# carl_ripup_2v42.net
KiCad netlist of a schematic drawn in EAGLE
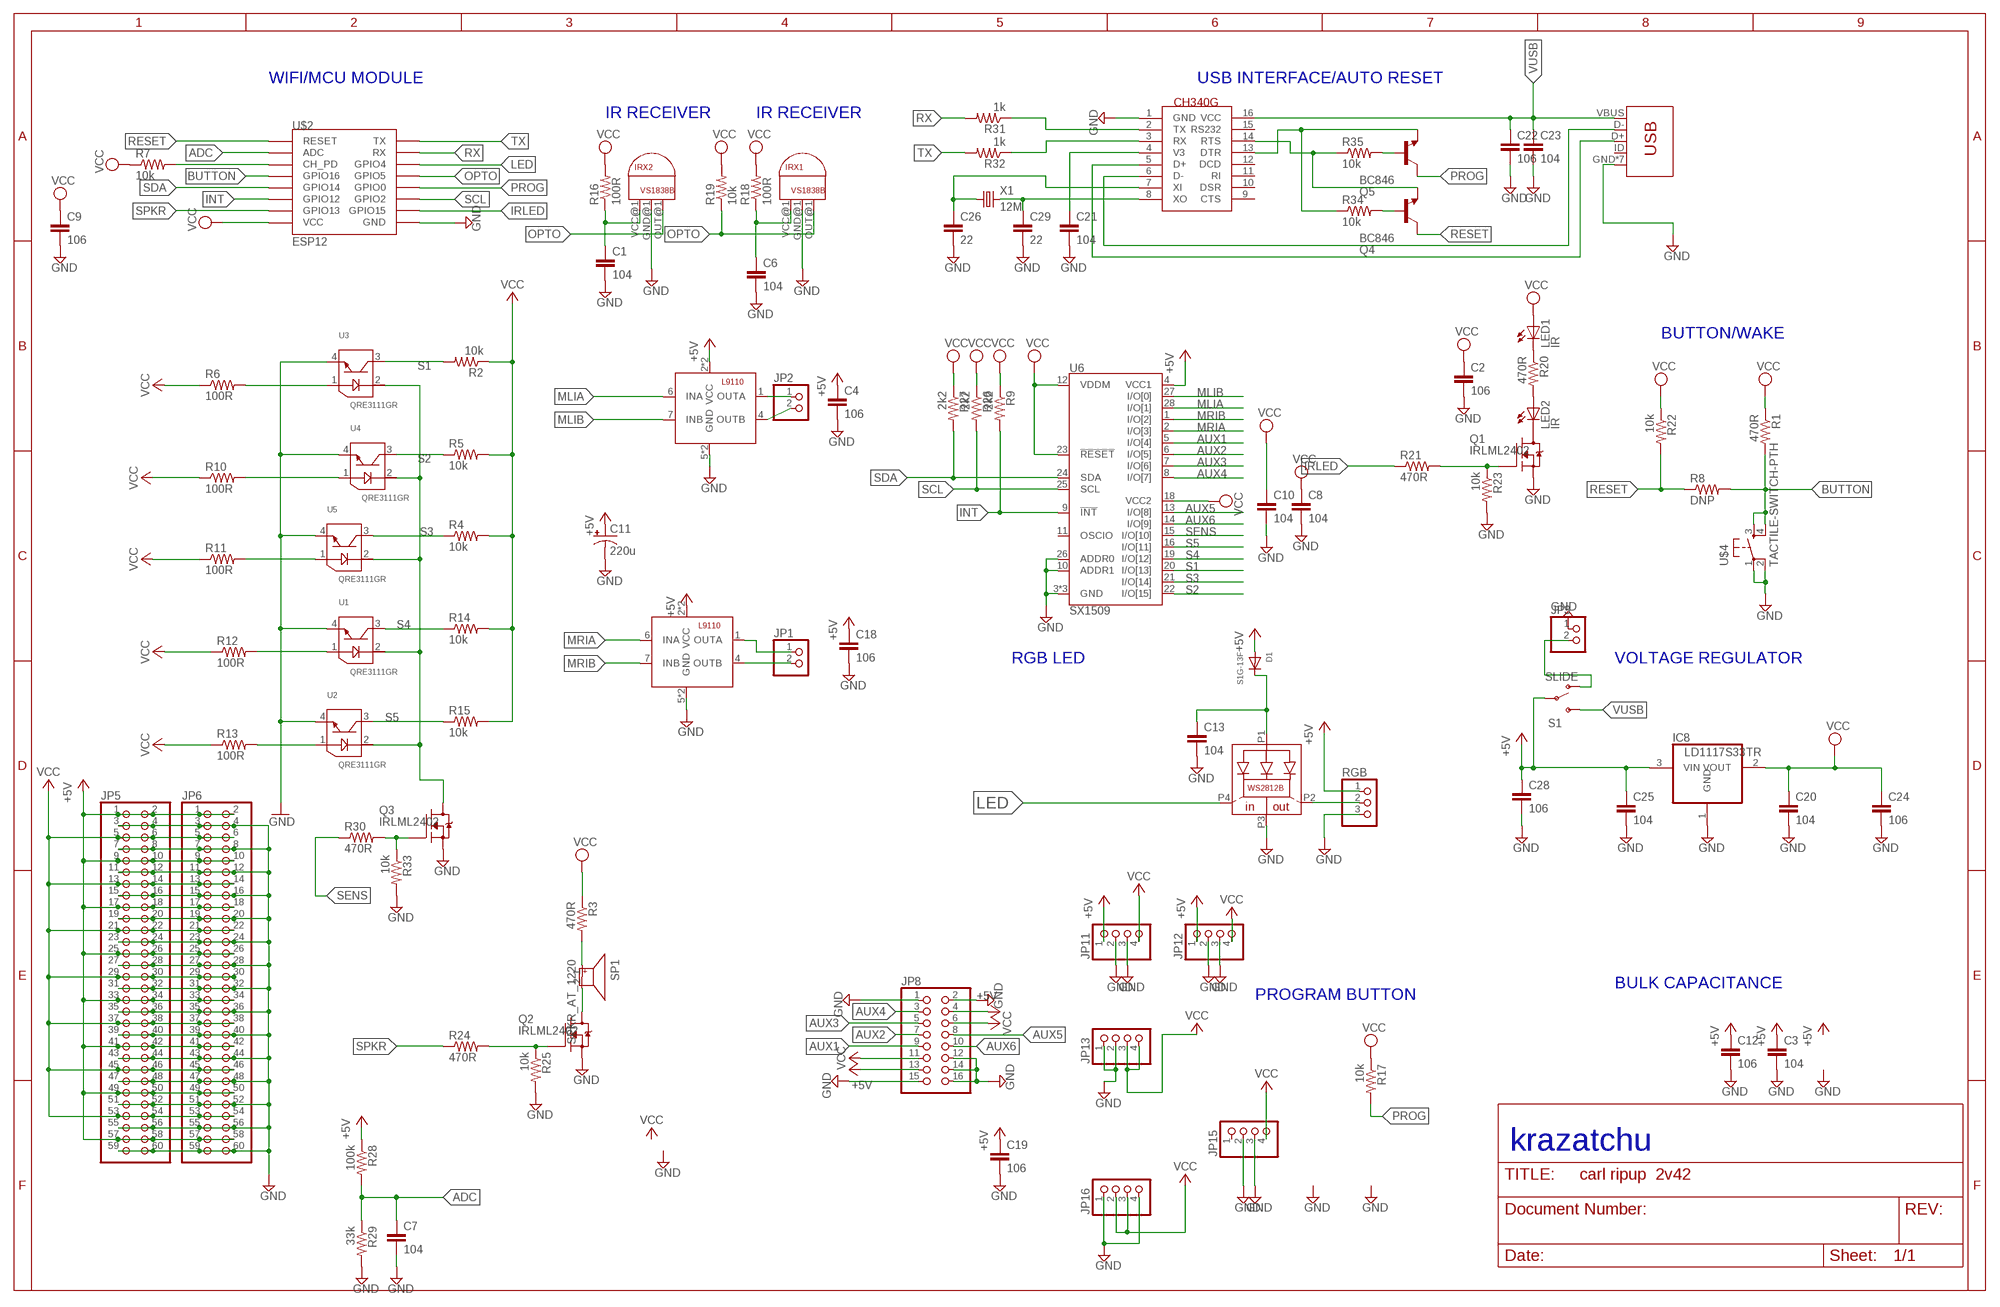
[diagram p0: schematic, sheet 1]

(export (version "E")
  (design (tool "Eeschema 10.0.6"))
  (components
    (comp (ref "C1")
      (value "104")
      (footprint "eagle-import:C0805")
      (libsource (lib "eagle-import") (part "C-EUC0805"))
    )
    (comp (ref "C2")
      (value "106")
      (footprint "eagle-import:C0805")
      (libsource (lib "eagle-import") (part "C-EUC0805"))
    )
    (comp (ref "C3")
      (value "104")
      (footprint "eagle-import:C0805")
      (libsource (lib "eagle-import") (part "C-EUC0805"))
    )
    (comp (ref "C4")
      (value "106")
      (footprint "eagle-import:C0805")
      (libsource (lib "eagle-import") (part "C-EUC0805"))
    )
    (comp (ref "C6")
      (value "104")
      (footprint "eagle-import:C0805")
      (libsource (lib "eagle-import") (part "C-EUC0805"))
    )
    (comp (ref "C7")
      (value "104")
      (footprint "eagle-import:C0805")
      (libsource (lib "eagle-import") (part "C-EUC0805"))
    )
    (comp (ref "C8")
      (value "104")
      (footprint "eagle-import:C0805")
      (libsource (lib "eagle-import") (part "C-EUC0805"))
    )
    (comp (ref "C9")
      (value "106")
      (footprint "eagle-import:C0805")
      (libsource (lib "eagle-import") (part "C-EUC0805"))
    )
    (comp (ref "C10")
      (value "104")
      (footprint "eagle-import:C0805")
      (libsource (lib "eagle-import") (part "C-EUC0805"))
    )
    (comp (ref "C11")
      (value "220u")
      (footprint "eagle-import:140CLH-0810")
      (libsource (lib "eagle-import") (part "CPOL-US140CLH-0810"))
    )
    (comp (ref "C12")
      (value "106")
      (footprint "eagle-import:C0805")
      (libsource (lib "eagle-import") (part "C-EUC0805"))
    )
    (comp (ref "C13")
      (value "104")
      (footprint "eagle-import:C0805")
      (libsource (lib "eagle-import") (part "C-EUC0805"))
    )
    (comp (ref "C18")
      (value "106")
      (footprint "eagle-import:C0805")
      (libsource (lib "eagle-import") (part "C-EUC0805"))
    )
    (comp (ref "C19")
      (value "106")
      (footprint "eagle-import:C0805")
      (libsource (lib "eagle-import") (part "C-EUC0805"))
    )
    (comp (ref "C20")
      (value "104")
      (footprint "eagle-import:C0805")
      (libsource (lib "eagle-import") (part "C-EUC0805"))
    )
    (comp (ref "C21")
      (value "104")
      (footprint "eagle-import:C0805")
      (libsource (lib "eagle-import") (part "C-EUC0805"))
    )
    (comp (ref "C22")
      (value "106")
      (footprint "eagle-import:C0805")
      (libsource (lib "eagle-import") (part "C-EUC0805"))
    )
    (comp (ref "C23")
      (value "104")
      (footprint "eagle-import:C0805")
      (libsource (lib "eagle-import") (part "C-EUC0805"))
    )
    (comp (ref "C24")
      (value "106")
      (footprint "eagle-import:C0805")
      (libsource (lib "eagle-import") (part "C-EUC0805"))
    )
    (comp (ref "C25")
      (value "104")
      (footprint "eagle-import:C0805")
      (libsource (lib "eagle-import") (part "C-EUC0805"))
    )
    (comp (ref "C26")
      (value "22")
      (footprint "eagle-import:C0805")
      (libsource (lib "eagle-import") (part "C-EUC0805"))
    )
    (comp (ref "C28")
      (value "106")
      (footprint "eagle-import:C0805")
      (libsource (lib "eagle-import") (part "C-EUC0805"))
    )
    (comp (ref "C29")
      (value "22")
      (footprint "eagle-import:C0805")
      (libsource (lib "eagle-import") (part "C-EUC0805"))
    )
    (comp (ref "D1")
      (value "S1G-13F")
      (footprint "eagle-import:SMADIODE")
      (libsource (lib "eagle-import") (part "DIODESMA"))
    )
    (comp (ref "IC1")
      (value "L9110")
      (footprint "eagle-import:SOIC8")
      (libsource (lib "eagle-import") (part "L9110"))
    )
    (comp (ref "IC2")
      (value "L9110")
      (footprint "eagle-import:SOIC8")
      (libsource (lib "eagle-import") (part "L9110"))
    )
    (comp (ref "IC8")
      (value "LD1117S33TR")
      (footprint "eagle-import:SOT223")
      (fields (field (name "MPN") "REG1117"))
      (libsource (lib "eagle-import") (part "REG1117"))
    )
    (comp (ref "IRX1")
      (value "VS1838B")
      (footprint "eagle-import:IR-RX-SINGLE")
      (libsource (lib "eagle-import") (part "IR-RX"))
    )
    (comp (ref "IRX2")
      (value "VS1838B")
      (footprint "eagle-import:IR-RX-SINGLE")
      (libsource (lib "eagle-import") (part "IR-RX"))
    )
    (comp (ref "JP1")
      (value "PINHD-1X2")
      (footprint "eagle-import:1X02")
      (libsource (lib "eagle-import") (part "PINHD-1X2"))
    )
    (comp (ref "JP2")
      (value "PINHD-1X2")
      (footprint "eagle-import:1X02")
      (libsource (lib "eagle-import") (part "PINHD-1X2"))
    )
    (comp (ref "JP3")
      (value "PINHD-1X2")
      (footprint "eagle-import:1X02")
      (libsource (lib "eagle-import") (part "PINHD-1X2"))
    )
    (comp (ref "JP5")
      (value "PINHD-2X30")
      (footprint "eagle-import:2X30")
      (libsource (lib "eagle-import") (part "PINHD-2X30"))
    )
    (comp (ref "JP6")
      (value "PINHD-2X30")
      (footprint "eagle-import:2X30")
      (libsource (lib "eagle-import") (part "PINHD-2X30"))
    )
    (comp (ref "JP8")
      (value "PINHD-2X8")
      (footprint "eagle-import:2X08")
      (libsource (lib "eagle-import") (part "PINHD-2X8"))
    )
    (comp (ref "JP11")
      (value "PINHD-1X4")
      (footprint "eagle-import:1X04")
      (libsource (lib "eagle-import") (part "PINHD-1X4"))
    )
    (comp (ref "JP12")
      (value "PINHD-1X4")
      (footprint "eagle-import:1X04")
      (libsource (lib "eagle-import") (part "PINHD-1X4"))
    )
    (comp (ref "JP13")
      (value "PINHD-1X4")
      (footprint "eagle-import:1X04")
      (libsource (lib "eagle-import") (part "PINHD-1X4"))
    )
    (comp (ref "JP15")
      (value "PINHD-1X4")
      (footprint "eagle-import:1X04")
      (libsource (lib "eagle-import") (part "PINHD-1X4"))
    )
    (comp (ref "JP16")
      (value "PINHD-1X4")
      (footprint "eagle-import:1X04")
      (libsource (lib "eagle-import") (part "PINHD-1X4"))
    )
    (comp (ref "LED1")
      (value "IR")
      (footprint "eagle-import:LED5MM")
      (libsource (lib "eagle-import") (part "LED5MM"))
    )
    (comp (ref "LED2")
      (value "IR")
      (footprint "eagle-import:LED5MM")
      (libsource (lib "eagle-import") (part "LED5MM"))
    )
    (comp (ref "Q1")
      (value "IRLML2402")
      (footprint "eagle-import:SOT23")
      (libsource (lib "eagle-import") (part "IRLML2402"))
    )
    (comp (ref "Q2")
      (value "IRLML2402")
      (footprint "eagle-import:SOT23")
      (libsource (lib "eagle-import") (part "IRLML2402"))
    )
    (comp (ref "Q3")
      (value "IRLML2402")
      (footprint "eagle-import:SOT23")
      (libsource (lib "eagle-import") (part "IRLML2402"))
    )
    (comp (ref "Q4")
      (value "BC846")
      (footprint "eagle-import:SOT23")
      (libsource (lib "eagle-import") (part "BC846"))
    )
    (comp (ref "Q5")
      (value "BC846")
      (footprint "eagle-import:SOT23")
      (libsource (lib "eagle-import") (part "BC846"))
    )
    (comp (ref "R1")
      (value "470R")
      (footprint "eagle-import:R0805")
      (libsource (lib "eagle-import") (part "rcl_R-US_R0805"))
    )
    (comp (ref "R2")
      (value "10k")
      (footprint "eagle-import:R0805")
      (libsource (lib "eagle-import") (part "R-US_R0805"))
    )
    (comp (ref "R3")
      (value "470R")
      (footprint "eagle-import:R0805")
      (libsource (lib "eagle-import") (part "rcl_R-US_R0805"))
    )
    (comp (ref "R4")
      (value "10k")
      (footprint "eagle-import:R0805")
      (libsource (lib "eagle-import") (part "R-US_R0805"))
    )
    (comp (ref "R5")
      (value "10k")
      (footprint "eagle-import:R0805")
      (libsource (lib "eagle-import") (part "R-US_R0805"))
    )
    (comp (ref "R6")
      (value "100R")
      (footprint "eagle-import:R0805")
      (libsource (lib "eagle-import") (part "R-US_R0805"))
    )
    (comp (ref "R7")
      (value "10k")
      (footprint "eagle-import:R0805")
      (libsource (lib "eagle-import") (part "rcl_R-US_R0805"))
    )
    (comp (ref "R8")
      (value "DNP")
      (footprint "eagle-import:R0805")
      (libsource (lib "eagle-import") (part "rcl_R-US_R0805"))
    )
    (comp (ref "R9")
      (value "2k2")
      (footprint "eagle-import:R0805")
      (libsource (lib "eagle-import") (part "rcl_R-US_R0805"))
    )
    (comp (ref "R10")
      (value "100R")
      (footprint "eagle-import:R0805")
      (libsource (lib "eagle-import") (part "R-US_R0805"))
    )
    (comp (ref "R11")
      (value "100R")
      (footprint "eagle-import:R0805")
      (libsource (lib "eagle-import") (part "R-US_R0805"))
    )
    (comp (ref "R12")
      (value "100R")
      (footprint "eagle-import:R0805")
      (libsource (lib "eagle-import") (part "R-US_R0805"))
    )
    (comp (ref "R13")
      (value "100R")
      (footprint "eagle-import:R0805")
      (libsource (lib "eagle-import") (part "R-US_R0805"))
    )
    (comp (ref "R14")
      (value "10k")
      (footprint "eagle-import:R0805")
      (libsource (lib "eagle-import") (part "R-US_R0805"))
    )
    (comp (ref "R15")
      (value "10k")
      (footprint "eagle-import:R0805")
      (libsource (lib "eagle-import") (part "R-US_R0805"))
    )
    (comp (ref "R16")
      (value "100R")
      (footprint "eagle-import:R0805")
      (libsource (lib "eagle-import") (part "rcl_R-US_R0805"))
    )
    (comp (ref "R17")
      (value "10k")
      (footprint "eagle-import:R0805")
      (libsource (lib "eagle-import") (part "rcl_R-US_R0805"))
    )
    (comp (ref "R18")
      (value "100R")
      (footprint "eagle-import:R0805")
      (libsource (lib "eagle-import") (part "rcl_R-US_R0805"))
    )
    (comp (ref "R19")
      (value "10k")
      (footprint "eagle-import:R0805")
      (libsource (lib "eagle-import") (part "rcl_R-US_R0805"))
    )
    (comp (ref "R20")
      (value "470R")
      (footprint "eagle-import:R0805")
      (libsource (lib "eagle-import") (part "rcl_R-US_R0805"))
    )
    (comp (ref "R21")
      (value "470R")
      (footprint "eagle-import:R0805")
      (libsource (lib "eagle-import") (part "rcl_R-US_R0805"))
    )
    (comp (ref "R22")
      (value "10k")
      (footprint "eagle-import:R0805")
      (libsource (lib "eagle-import") (part "rcl_R-US_R0805"))
    )
    (comp (ref "R23")
      (value "10k")
      (footprint "eagle-import:R0805")
      (libsource (lib "eagle-import") (part "rcl_R-US_R0805"))
    )
    (comp (ref "R24")
      (value "470R")
      (footprint "eagle-import:R0805")
      (libsource (lib "eagle-import") (part "rcl_R-US_R0805"))
    )
    (comp (ref "R25")
      (value "10k")
      (footprint "eagle-import:R0805")
      (libsource (lib "eagle-import") (part "rcl_R-US_R0805"))
    )
    (comp (ref "R26")
      (value "2k2")
      (footprint "eagle-import:R0805")
      (libsource (lib "eagle-import") (part "rcl_R-US_R0805"))
    )
    (comp (ref "R27")
      (value "2k2")
      (footprint "eagle-import:R0805")
      (libsource (lib "eagle-import") (part "rcl_R-US_R0805"))
    )
    (comp (ref "R28")
      (value "100k")
      (footprint "eagle-import:R0805")
      (libsource (lib "eagle-import") (part "rcl_R-US_R0805"))
    )
    (comp (ref "R29")
      (value "33k")
      (footprint "eagle-import:R0805")
      (libsource (lib "eagle-import") (part "rcl_R-US_R0805"))
    )
    (comp (ref "R30")
      (value "470R")
      (footprint "eagle-import:R0805")
      (libsource (lib "eagle-import") (part "rcl_R-US_R0805"))
    )
    (comp (ref "R31")
      (value "1k")
      (footprint "eagle-import:R0805")
      (libsource (lib "eagle-import") (part "rcl_R-US_R0805"))
    )
    (comp (ref "R32")
      (value "1k")
      (footprint "eagle-import:R0805")
      (libsource (lib "eagle-import") (part "rcl_R-US_R0805"))
    )
    (comp (ref "R33")
      (value "10k")
      (footprint "eagle-import:R0805")
      (libsource (lib "eagle-import") (part "rcl_R-US_R0805"))
    )
    (comp (ref "R34")
      (value "10k")
      (footprint "eagle-import:R0805")
      (libsource (lib "eagle-import") (part "rcl_R-US_R0805"))
    )
    (comp (ref "R35")
      (value "10k")
      (footprint "eagle-import:R0805")
      (libsource (lib "eagle-import") (part "rcl_R-US_R0805"))
    )
    (comp (ref "RGB")
      (value "PINHD-1X3RND")
      (footprint "eagle-import:1X03_ROUND")
      (libsource (lib "eagle-import") (part "PINHD-1X3RND"))
    )
    (comp (ref "RGB1")
      (value "ws2812b")
      (footprint "eagle-import:PLCC_4_5050_TRIM")
      (libsource (lib "eagle-import") (part "WS2812B"))
    )
    (comp (ref "S1")
      (value "SLIDE")
      (footprint "eagle-import:SWITCH-SPDT")
      (libsource (lib "eagle-import") (part "SWITCH-SPDTPTH"))
    )
    (comp (ref "SP1")
      (value "SPKR_AT_1220")
      (footprint "eagle-import:TRANSDUCER_12_6")
      (libsource (lib "eagle-import") (part "SPKR_AT_1220"))
    )
    (comp (ref "U$2")
      (value "ESP12")
      (footprint "eagle-import:ESP12")
      (libsource (lib "eagle-import") (part "ESP12"))
    )
    (comp (ref "U$4")
      (value "TACTILE-SWITCH-PTH")
      (footprint "eagle-import:TAC-SWITCH-PTH")
      (libsource (lib "eagle-import") (part "TACTILE-SWITCH-PTH"))
    )
    (comp (ref "U$5")
      (value "CH340G")
      (footprint "eagle-import:SOIC16")
      (libsource (lib "eagle-import") (part "CH340G"))
    )
    (comp (ref "U1")
      (value "QRE3111GR")
      (footprint "eagle-import:QRE1113GR")
      (libsource (lib "eagle-import") (part "QRE3111GR"))
    )
    (comp (ref "U2")
      (value "QRE3111GR")
      (footprint "eagle-import:QRE1113GR")
      (libsource (lib "eagle-import") (part "QRE3111GR"))
    )
    (comp (ref "U3")
      (value "QRE3111GR")
      (footprint "eagle-import:QRE1113GR")
      (libsource (lib "eagle-import") (part "QRE3111GR"))
    )
    (comp (ref "U4")
      (value "QRE3111GR")
      (footprint "eagle-import:QRE1113GR")
      (libsource (lib "eagle-import") (part "QRE3111GR"))
    )
    (comp (ref "U5")
      (value "QRE3111GR")
      (footprint "eagle-import:QRE1113GR")
      (libsource (lib "eagle-import") (part "QRE3111GR"))
    )
    (comp (ref "U6")
      (value "SX1509")
      (footprint "eagle-import:QFN-28")
      (libsource (lib "eagle-import") (part "SX1509"))
    )
    (comp (ref "USB1")
      (value "USB_MICROB-10118194-0001LF")
      (footprint "eagle-import:USB-MICRO-B")
      (libsource (lib "eagle-import") (part "USB_MICROB-10118194-0001LF"))
    )
    (comp (ref "X1")
      (value "12M")
      (footprint "eagle-import:HC49UP")
      (libsource (lib "eagle-import") (part "CRYSTALHC49UP"))
    )
  )
  (nets
    (net (code "1") (name "+5V") (class "Default")
      (node (ref "C11") (pin "+") (pinfunction "+_+") (pintype "passive"))
      (node (ref "C12") (pin "1") (pinfunction "1_1") (pintype "passive"))
      (node (ref "C18") (pin "1") (pinfunction "1_1") (pintype "passive"))
      (node (ref "C19") (pin "1") (pinfunction "1_1") (pintype "passive"))
      (node (ref "C25") (pin "1") (pinfunction "1_1") (pintype "passive"))
      (node (ref "C28") (pin "1") (pinfunction "1_1") (pintype "passive"))
      (node (ref "C3") (pin "1") (pinfunction "1_1") (pintype "passive"))
      (node (ref "C4") (pin "1") (pinfunction "1_1") (pintype "passive"))
      (node (ref "D1") (pin "A") (pinfunction "A_A") (pintype "passive"))
      (node (ref "IC1") (pin "2") (pinfunction "VCC_2") (pintype "bidirectional"))
      (node (ref "IC1") (pin "3") (pinfunction "VCC_3") (pintype "bidirectional"))
      (node (ref "IC2") (pin "2") (pinfunction "VCC_2") (pintype "bidirectional"))
      (node (ref "IC2") (pin "3") (pinfunction "VCC_3") (pintype "bidirectional"))
      (node (ref "IC8") (pin "3") (pinfunction "VIN_3") (pintype "input"))
      (node (ref "JP11") (pin "1") (pinfunction "1_1") (pintype "passive"))
      (node (ref "JP12") (pin "1") (pinfunction "1_1") (pintype "passive"))
      (node (ref "JP5") (pin "1") (pinfunction "1_1") (pintype "passive"))
      (node (ref "JP5") (pin "10") (pinfunction "10_10") (pintype "passive"))
      (node (ref "JP5") (pin "17") (pinfunction "17_17") (pintype "passive"))
      (node (ref "JP5") (pin "18") (pinfunction "18_18") (pintype "passive"))
      (node (ref "JP5") (pin "2") (pinfunction "2_2") (pintype "passive"))
      (node (ref "JP5") (pin "25") (pinfunction "25_25") (pintype "passive"))
      (node (ref "JP5") (pin "26") (pinfunction "26_26") (pintype "passive"))
      (node (ref "JP5") (pin "33") (pinfunction "33_33") (pintype "passive"))
      (node (ref "JP5") (pin "34") (pinfunction "34_34") (pintype "passive"))
      (node (ref "JP5") (pin "41") (pinfunction "41_41") (pintype "passive"))
      (node (ref "JP5") (pin "42") (pinfunction "42_42") (pintype "passive"))
      (node (ref "JP5") (pin "49") (pinfunction "49_49") (pintype "passive"))
      (node (ref "JP5") (pin "50") (pinfunction "50_50") (pintype "passive"))
      (node (ref "JP5") (pin "57") (pinfunction "57_57") (pintype "passive"))
      (node (ref "JP5") (pin "58") (pinfunction "58_58") (pintype "passive"))
      (node (ref "JP5") (pin "9") (pinfunction "9_9") (pintype "passive"))
      (node (ref "JP6") (pin "1") (pinfunction "1_1") (pintype "passive"))
      (node (ref "JP6") (pin "10") (pinfunction "10_10") (pintype "passive"))
      (node (ref "JP6") (pin "17") (pinfunction "17_17") (pintype "passive"))
      (node (ref "JP6") (pin "18") (pinfunction "18_18") (pintype "passive"))
      (node (ref "JP6") (pin "2") (pinfunction "2_2") (pintype "passive"))
      (node (ref "JP6") (pin "25") (pinfunction "25_25") (pintype "passive"))
      (node (ref "JP6") (pin "26") (pinfunction "26_26") (pintype "passive"))
      (node (ref "JP6") (pin "33") (pinfunction "33_33") (pintype "passive"))
      (node (ref "JP6") (pin "34") (pinfunction "34_34") (pintype "passive"))
      (node (ref "JP6") (pin "41") (pinfunction "41_41") (pintype "passive"))
      (node (ref "JP6") (pin "42") (pinfunction "42_42") (pintype "passive"))
      (node (ref "JP6") (pin "49") (pinfunction "49_49") (pintype "passive"))
      (node (ref "JP6") (pin "50") (pinfunction "50_50") (pintype "passive"))
      (node (ref "JP6") (pin "57") (pinfunction "57_57") (pintype "passive"))
      (node (ref "JP6") (pin "58") (pinfunction "58_58") (pintype "passive"))
      (node (ref "JP6") (pin "9") (pinfunction "9_9") (pintype "passive"))
      (node (ref "JP8") (pin "13") (pinfunction "13_13") (pintype "passive"))
      (node (ref "JP8") (pin "4") (pinfunction "4_4") (pintype "passive"))
      (node (ref "R28") (pin "1") (pinfunction "1_1") (pintype "passive"))
      (node (ref "RGB") (pin "1") (pinfunction "1_1") (pintype "passive"))
      (node (ref "S1") (pin "2") (pinfunction "P_2") (pintype "passive"))
      (node (ref "U6") (pin "4") (pinfunction "VCC1_4") (pintype "bidirectional"))
    )
    (net (code "2") (name "/S1") (class "Default")
      (node (ref "R2") (pin "2") (pinfunction "2_2") (pintype "passive"))
      (node (ref "U3") (pin "3") (pinfunction "3_3") (pintype "bidirectional"))
      (node (ref "U6") (pin "20") (pinfunction "I/O[13]_20") (pintype "bidirectional"))
    )
    (net (code "3") (name "/S2") (class "Default")
      (node (ref "R5") (pin "1") (pinfunction "1_1") (pintype "passive"))
      (node (ref "U4") (pin "3") (pinfunction "3_3") (pintype "bidirectional"))
      (node (ref "U6") (pin "22") (pinfunction "I/O[15]_22") (pintype "bidirectional"))
    )
    (net (code "4") (name "/S3") (class "Default")
      (node (ref "R4") (pin "1") (pinfunction "1_1") (pintype "passive"))
      (node (ref "U5") (pin "3") (pinfunction "3_3") (pintype "bidirectional"))
      (node (ref "U6") (pin "21") (pinfunction "I/O[14]_21") (pintype "bidirectional"))
    )
    (net (code "5") (name "/S4") (class "Default")
      (node (ref "R14") (pin "1") (pinfunction "1_1") (pintype "passive"))
      (node (ref "U1") (pin "3") (pinfunction "3_3") (pintype "bidirectional"))
      (node (ref "U6") (pin "19") (pinfunction "I/O[12]_19") (pintype "bidirectional"))
    )
    (net (code "6") (name "/S5") (class "Default")
      (node (ref "R15") (pin "1") (pinfunction "1_1") (pintype "passive"))
      (node (ref "U2") (pin "3") (pinfunction "3_3") (pintype "bidirectional"))
      (node (ref "U6") (pin "16") (pinfunction "I/O[11]_16") (pintype "bidirectional"))
    )
    (net (code "7") (name "ADC") (class "Default")
      (node (ref "C7") (pin "1") (pinfunction "1_1") (pintype "passive"))
      (node (ref "R28") (pin "2") (pinfunction "2_2") (pintype "passive"))
      (node (ref "R29") (pin "1") (pinfunction "1_1") (pintype "passive"))
      (node (ref "U$2") (pin "ADC") (pinfunction "ADC_ADC") (pintype "bidirectional"))
    )
    (net (code "8") (name "AUX1") (class "Default")
      (node (ref "JP8") (pin "9") (pinfunction "9_9") (pintype "passive"))
      (node (ref "U6") (pin "5") (pinfunction "I/O[4]_5") (pintype "bidirectional"))
    )
    (net (code "9") (name "AUX2") (class "Default")
      (node (ref "JP8") (pin "7") (pinfunction "7_7") (pintype "passive"))
      (node (ref "U6") (pin "6") (pinfunction "I/O[5]_6") (pintype "bidirectional"))
    )
    (net (code "10") (name "AUX3") (class "Default")
      (node (ref "JP8") (pin "5") (pinfunction "5_5") (pintype "passive"))
      (node (ref "U6") (pin "7") (pinfunction "I/O[6]_7") (pintype "bidirectional"))
    )
    (net (code "11") (name "AUX4") (class "Default")
      (node (ref "JP8") (pin "3") (pinfunction "3_3") (pintype "passive"))
      (node (ref "U6") (pin "8") (pinfunction "I/O[7]_8") (pintype "bidirectional"))
    )
    (net (code "12") (name "AUX5") (class "Default")
      (node (ref "JP8") (pin "8") (pinfunction "8_8") (pintype "passive"))
      (node (ref "U6") (pin "13") (pinfunction "I/O[8]_13") (pintype "bidirectional"))
    )
    (net (code "13") (name "AUX6") (class "Default")
      (node (ref "JP8") (pin "10") (pinfunction "10_10") (pintype "passive"))
      (node (ref "U6") (pin "14") (pinfunction "I/O[9]_14") (pintype "bidirectional"))
    )
    (net (code "14") (name "BUTTON") (class "Default")
      (node (ref "R1") (pin "2") (pinfunction "2_2") (pintype "passive"))
      (node (ref "R8") (pin "2") (pinfunction "2_2") (pintype "passive"))
      (node (ref "U$2") (pin "GPIO16") (pinfunction "GPIO16_GPIO16") (pintype "bidirectional"))
      (node (ref "U$4") (pin "3") (pinfunction "3_3") (pintype "passive"))
      (node (ref "U$4") (pin "4") (pinfunction "4_4") (pintype "passive"))
    )
    (net (code "15") (name "GND") (class "Default")
      (node (ref "C1") (pin "2") (pinfunction "2_2") (pintype "passive"))
      (node (ref "C10") (pin "2") (pinfunction "2_2") (pintype "passive"))
      (node (ref "C11") (pin "-") (pinfunction "-_-") (pintype "passive"))
      (node (ref "C12") (pin "2") (pinfunction "2_2") (pintype "passive"))
      (node (ref "C13") (pin "2") (pinfunction "2_2") (pintype "passive"))
      (node (ref "C18") (pin "2") (pinfunction "2_2") (pintype "passive"))
      (node (ref "C19") (pin "2") (pinfunction "2_2") (pintype "passive"))
      (node (ref "C2") (pin "2") (pinfunction "2_2") (pintype "passive"))
      (node (ref "C20") (pin "2") (pinfunction "2_2") (pintype "passive"))
      (node (ref "C21") (pin "2") (pinfunction "2_2") (pintype "passive"))
      (node (ref "C22") (pin "2") (pinfunction "2_2") (pintype "passive"))
      (node (ref "C23") (pin "2") (pinfunction "2_2") (pintype "passive"))
      (node (ref "C24") (pin "2") (pinfunction "2_2") (pintype "passive"))
      (node (ref "C25") (pin "2") (pinfunction "2_2") (pintype "passive"))
      (node (ref "C26") (pin "2") (pinfunction "2_2") (pintype "passive"))
      (node (ref "C28") (pin "2") (pinfunction "2_2") (pintype "passive"))
      (node (ref "C29") (pin "2") (pinfunction "2_2") (pintype "passive"))
      (node (ref "C3") (pin "2") (pinfunction "2_2") (pintype "passive"))
      (node (ref "C4") (pin "2") (pinfunction "2_2") (pintype "passive"))
      (node (ref "C6") (pin "2") (pinfunction "2_2") (pintype "passive"))
      (node (ref "C7") (pin "2") (pinfunction "2_2") (pintype "passive"))
      (node (ref "C8") (pin "2") (pinfunction "2_2") (pintype "passive"))
      (node (ref "C9") (pin "2") (pinfunction "2_2") (pintype "passive"))
      (node (ref "IC1") (pin "5") (pinfunction "GND_5") (pintype "bidirectional"))
      (node (ref "IC1") (pin "8") (pinfunction "GND_8") (pintype "bidirectional"))
      (node (ref "IC2") (pin "5") (pinfunction "GND_5") (pintype "bidirectional"))
      (node (ref "IC2") (pin "8") (pinfunction "GND_8") (pintype "bidirectional"))
      (node (ref "IC8") (pin "1") (pinfunction "GND_1") (pintype "power_in"))
      (node (ref "IRX1") (pin "GND@1") (pinfunction "GND_GND@1") (pintype "bidirectional"))
      (node (ref "IRX2") (pin "GND@1") (pinfunction "GND_GND@1") (pintype "bidirectional"))
      (node (ref "JP11") (pin "2") (pinfunction "2_2") (pintype "passive"))
      (node (ref "JP11") (pin "3") (pinfunction "3_3") (pintype "passive"))
      (node (ref "JP12") (pin "2") (pinfunction "2_2") (pintype "passive"))
      (node (ref "JP12") (pin "3") (pinfunction "3_3") (pintype "passive"))
      (node (ref "JP13") (pin "1") (pinfunction "1_1") (pintype "passive"))
      (node (ref "JP13") (pin "2") (pinfunction "2_2") (pintype "passive"))
      (node (ref "JP15") (pin "2") (pinfunction "2_2") (pintype "passive"))
      (node (ref "JP15") (pin "3") (pinfunction "3_3") (pintype "passive"))
      (node (ref "JP16") (pin "1") (pinfunction "1_1") (pintype "passive"))
      (node (ref "JP16") (pin "4") (pinfunction "4_4") (pintype "passive"))
      (node (ref "JP3") (pin "1") (pinfunction "1_1") (pintype "passive"))
      (node (ref "JP5") (pin "11") (pinfunction "11_11") (pintype "passive"))
      (node (ref "JP5") (pin "12") (pinfunction "12_12") (pintype "passive"))
      (node (ref "JP5") (pin "15") (pinfunction "15_15") (pintype "passive"))
      (node (ref "JP5") (pin "16") (pinfunction "16_16") (pintype "passive"))
      (node (ref "JP5") (pin "19") (pinfunction "19_19") (pintype "passive"))
      (node (ref "JP5") (pin "20") (pinfunction "20_20") (pintype "passive"))
      (node (ref "JP5") (pin "23") (pinfunction "23_23") (pintype "passive"))
      (node (ref "JP5") (pin "24") (pinfunction "24_24") (pintype "passive"))
      (node (ref "JP5") (pin "27") (pinfunction "27_27") (pintype "passive"))
      (node (ref "JP5") (pin "28") (pinfunction "28_28") (pintype "passive"))
      (node (ref "JP5") (pin "3") (pinfunction "3_3") (pintype "passive"))
      (node (ref "JP5") (pin "31") (pinfunction "31_31") (pintype "passive"))
      (node (ref "JP5") (pin "32") (pinfunction "32_32") (pintype "passive"))
      (node (ref "JP5") (pin "35") (pinfunction "35_35") (pintype "passive"))
      (node (ref "JP5") (pin "36") (pinfunction "36_36") (pintype "passive"))
      (node (ref "JP5") (pin "39") (pinfunction "39_39") (pintype "passive"))
      (node (ref "JP5") (pin "4") (pinfunction "4_4") (pintype "passive"))
      (node (ref "JP5") (pin "40") (pinfunction "40_40") (pintype "passive"))
      (node (ref "JP5") (pin "43") (pinfunction "43_43") (pintype "passive"))
      (node (ref "JP5") (pin "44") (pinfunction "44_44") (pintype "passive"))
      (node (ref "JP5") (pin "47") (pinfunction "47_47") (pintype "passive"))
      (node (ref "JP5") (pin "48") (pinfunction "48_48") (pintype "passive"))
      (node (ref "JP5") (pin "51") (pinfunction "51_51") (pintype "passive"))
      (node (ref "JP5") (pin "52") (pinfunction "52_52") (pintype "passive"))
      (node (ref "JP5") (pin "55") (pinfunction "55_55") (pintype "passive"))
      (node (ref "JP5") (pin "56") (pinfunction "56_56") (pintype "passive"))
      (node (ref "JP5") (pin "59") (pinfunction "59_59") (pintype "passive"))
      (node (ref "JP5") (pin "60") (pinfunction "60_60") (pintype "passive"))
      (node (ref "JP5") (pin "7") (pinfunction "7_7") (pintype "passive"))
      (node (ref "JP5") (pin "8") (pinfunction "8_8") (pintype "passive"))
      (node (ref "JP6") (pin "11") (pinfunction "11_11") (pintype "passive"))
      (node (ref "JP6") (pin "12") (pinfunction "12_12") (pintype "passive"))
      (node (ref "JP6") (pin "15") (pinfunction "15_15") (pintype "passive"))
      (node (ref "JP6") (pin "16") (pinfunction "16_16") (pintype "passive"))
      (node (ref "JP6") (pin "19") (pinfunction "19_19") (pintype "passive"))
      (node (ref "JP6") (pin "20") (pinfunction "20_20") (pintype "passive"))
      (node (ref "JP6") (pin "23") (pinfunction "23_23") (pintype "passive"))
      (node (ref "JP6") (pin "24") (pinfunction "24_24") (pintype "passive"))
      (node (ref "JP6") (pin "27") (pinfunction "27_27") (pintype "passive"))
      (node (ref "JP6") (pin "28") (pinfunction "28_28") (pintype "passive"))
      (node (ref "JP6") (pin "3") (pinfunction "3_3") (pintype "passive"))
      (node (ref "JP6") (pin "31") (pinfunction "31_31") (pintype "passive"))
      (node (ref "JP6") (pin "32") (pinfunction "32_32") (pintype "passive"))
      (node (ref "JP6") (pin "35") (pinfunction "35_35") (pintype "passive"))
      (node (ref "JP6") (pin "36") (pinfunction "36_36") (pintype "passive"))
      (node (ref "JP6") (pin "39") (pinfunction "39_39") (pintype "passive"))
      (node (ref "JP6") (pin "4") (pinfunction "4_4") (pintype "passive"))
      (node (ref "JP6") (pin "40") (pinfunction "40_40") (pintype "passive"))
      (node (ref "JP6") (pin "43") (pinfunction "43_43") (pintype "passive"))
      (node (ref "JP6") (pin "44") (pinfunction "44_44") (pintype "passive"))
      (node (ref "JP6") (pin "47") (pinfunction "47_47") (pintype "passive"))
      (node (ref "JP6") (pin "48") (pinfunction "48_48") (pintype "passive"))
      (node (ref "JP6") (pin "51") (pinfunction "51_51") (pintype "passive"))
      (node (ref "JP6") (pin "52") (pinfunction "52_52") (pintype "passive"))
      (node (ref "JP6") (pin "55") (pinfunction "55_55") (pintype "passive"))
      (node (ref "JP6") (pin "56") (pinfunction "56_56") (pintype "passive"))
      (node (ref "JP6") (pin "59") (pinfunction "59_59") (pintype "passive"))
      (node (ref "JP6") (pin "60") (pinfunction "60_60") (pintype "passive"))
      (node (ref "JP6") (pin "7") (pinfunction "7_7") (pintype "passive"))
      (node (ref "JP6") (pin "8") (pinfunction "8_8") (pintype "passive"))
      (node (ref "JP8") (pin "1") (pinfunction "1_1") (pintype "passive"))
      (node (ref "JP8") (pin "12") (pinfunction "12_12") (pintype "passive"))
      (node (ref "JP8") (pin "14") (pinfunction "14_14") (pintype "passive"))
      (node (ref "JP8") (pin "15") (pinfunction "15_15") (pintype "passive"))
      (node (ref "JP8") (pin "16") (pinfunction "16_16") (pintype "passive"))
      (node (ref "JP8") (pin "2") (pinfunction "2_2") (pintype "passive"))
      (node (ref "Q1") (pin "2") (pinfunction "S_2") (pintype "passive"))
      (node (ref "Q2") (pin "2") (pinfunction "S_2") (pintype "passive"))
      (node (ref "Q3") (pin "2") (pinfunction "S_2") (pintype "passive"))
      (node (ref "R23") (pin "2") (pinfunction "2_2") (pintype "passive"))
      (node (ref "R25") (pin "2") (pinfunction "2_2") (pintype "passive"))
      (node (ref "R29") (pin "2") (pinfunction "2_2") (pintype "passive"))
      (node (ref "R33") (pin "2") (pinfunction "2_2") (pintype "passive"))
      (node (ref "RGB") (pin "3") (pinfunction "3_3") (pintype "passive"))
      (node (ref "RGB1") (pin "P3") (pinfunction "GND_P3") (pintype "power_in"))
      (node (ref "U$2") (pin "GND") (pinfunction "GND_GND") (pintype "bidirectional"))
      (node (ref "U$4") (pin "1") (pinfunction "1_1") (pintype "passive"))
      (node (ref "U$4") (pin "2") (pinfunction "2_2") (pintype "passive"))
      (node (ref "U$5") (pin "1") (pinfunction "GND_1") (pintype "bidirectional"))
      (node (ref "U1") (pin "4") (pinfunction "4_4") (pintype "bidirectional"))
      (node (ref "U2") (pin "4") (pinfunction "4_4") (pintype "bidirectional"))
      (node (ref "U3") (pin "4") (pinfunction "4_4") (pintype "bidirectional"))
      (node (ref "U4") (pin "4") (pinfunction "4_4") (pintype "bidirectional"))
      (node (ref "U5") (pin "4") (pinfunction "4_4") (pintype "bidirectional"))
      (node (ref "U6") (pin "10") (pinfunction "ADDR1_10") (pintype "bidirectional"))
      (node (ref "U6") (pin "17") (pinfunction "GND_17") (pintype "bidirectional"))
      (node (ref "U6") (pin "26") (pinfunction "ADDR0_26") (pintype "bidirectional"))
      (node (ref "U6") (pin "29") (pinfunction "GND_29") (pintype "bidirectional"))
      (node (ref "U6") (pin "3") (pinfunction "GND_3") (pintype "bidirectional"))
      (node (ref "USB1") (pin "GND") (pinfunction "GND_GND") (pintype "bidirectional"))
      (node (ref "USB1") (pin "MT1") (pinfunction "GND_MT1") (pintype "bidirectional"))
      (node (ref "USB1") (pin "MT2") (pinfunction "GND_MT2") (pintype "bidirectional"))
      (node (ref "USB1") (pin "MT3") (pinfunction "GND_MT3") (pintype "bidirectional"))
      (node (ref "USB1") (pin "MT4") (pinfunction "GND_MT4") (pintype "bidirectional"))
      (node (ref "USB1") (pin "SMT3") (pinfunction "GND_SMT3") (pintype "bidirectional"))
      (node (ref "USB1") (pin "SMT4") (pinfunction "GND_SMT4") (pintype "bidirectional"))
    )
    (net (code "16") (name "INT") (class "Default")
      (node (ref "R9") (pin "2") (pinfunction "2_2") (pintype "passive"))
      (node (ref "U$2") (pin "GPIO12") (pinfunction "GPIO12_GPIO12") (pintype "bidirectional"))
      (node (ref "U6") (pin "9") (pinfunction "~{INT}_9") (pintype "bidirectional"))
    )
    (net (code "17") (name "IRLED") (class "Default")
      (node (ref "R21") (pin "1") (pinfunction "1_1") (pintype "passive"))
      (node (ref "U$2") (pin "GPIO15") (pinfunction "GPIO15_GPIO15") (pintype "bidirectional"))
    )
    (net (code "18") (name "LED") (class "Default")
      (node (ref "RGB1") (pin "P4") (pinfunction "DI_P4") (pintype "input"))
      (node (ref "U$2") (pin "GPIO4") (pinfunction "GPIO4_GPIO4") (pintype "bidirectional"))
    )
    (net (code "19") (name "MLIA") (class "Default")
      (node (ref "IC1") (pin "6") (pinfunction "INA_6") (pintype "bidirectional"))
      (node (ref "U6") (pin "28") (pinfunction "I/O[1]_28") (pintype "bidirectional"))
    )
    (net (code "20") (name "MLIB") (class "Default")
      (node (ref "IC1") (pin "7") (pinfunction "INB_7") (pintype "bidirectional"))
      (node (ref "U6") (pin "27") (pinfunction "I/O[0]_27") (pintype "bidirectional"))
    )
    (net (code "21") (name "MRIA") (class "Default")
      (node (ref "IC2") (pin "6") (pinfunction "INA_6") (pintype "bidirectional"))
      (node (ref "U6") (pin "2") (pinfunction "I/O[3]_2") (pintype "bidirectional"))
    )
    (net (code "22") (name "MRIB") (class "Default")
      (node (ref "IC2") (pin "7") (pinfunction "INB_7") (pintype "bidirectional"))
      (node (ref "U6") (pin "1") (pinfunction "I/O[2]_1") (pintype "bidirectional"))
    )
    (net (code "23") (name "Net-(IC1-OUTA)") (class "Default")
      (node (ref "IC1") (pin "1") (pinfunction "OUTA_1") (pintype "bidirectional"))
      (node (ref "JP2") (pin "1") (pinfunction "1_1") (pintype "passive"))
    )
    (net (code "24") (name "Net-(IC1-OUTB)") (class "Default")
      (node (ref "IC1") (pin "4") (pinfunction "OUTB_4") (pintype "bidirectional"))
      (node (ref "JP2") (pin "2") (pinfunction "2_2") (pintype "passive"))
    )
    (net (code "25") (name "Net-(IC2-OUTA)") (class "Default")
      (node (ref "IC2") (pin "1") (pinfunction "OUTA_1") (pintype "bidirectional"))
      (node (ref "JP1") (pin "1") (pinfunction "1_1") (pintype "passive"))
    )
    (net (code "26") (name "Net-(IC2-OUTB)") (class "Default")
      (node (ref "IC2") (pin "4") (pinfunction "OUTB_4") (pintype "bidirectional"))
      (node (ref "JP1") (pin "2") (pinfunction "2_2") (pintype "passive"))
    )
    (net (code "27") (name "Net-(IRX1-VCC)") (class "Default")
      (node (ref "C6") (pin "1") (pinfunction "1_1") (pintype "passive"))
      (node (ref "IRX1") (pin "VCC@1") (pinfunction "VCC_VCC@1") (pintype "bidirectional"))
      (node (ref "R18") (pin "1") (pinfunction "1_1") (pintype "passive"))
    )
    (net (code "28") (name "Net-(IRX2-VCC)") (class "Default")
      (node (ref "C1") (pin "1") (pinfunction "1_1") (pintype "passive"))
      (node (ref "IRX2") (pin "VCC@1") (pinfunction "VCC_VCC@1") (pintype "bidirectional"))
      (node (ref "R16") (pin "1") (pinfunction "1_1") (pintype "passive"))
    )
    (net (code "29") (name "Net-(LED1-C)") (class "Default")
      (node (ref "LED1") (pin "K") (pinfunction "C_K") (pintype "passive"))
      (node (ref "R20") (pin "1") (pinfunction "1_1") (pintype "passive"))
    )
    (net (code "30") (name "Net-(LED2-C)") (class "Default")
      (node (ref "LED2") (pin "K") (pinfunction "C_K") (pintype "passive"))
      (node (ref "Q1") (pin "3") (pinfunction "D_3") (pintype "passive"))
    )
    (net (code "31") (name "Net-(LED2-PadA)") (class "Default")
      (node (ref "LED2") (pin "A") (pinfunction "A_A") (pintype "passive"))
      (node (ref "R20") (pin "2") (pinfunction "2_2") (pintype "passive"))
    )
    (net (code "32") (name "Net-(Q1-G)") (class "Default")
      (node (ref "Q1") (pin "1") (pinfunction "G_1") (pintype "passive"))
      (node (ref "R21") (pin "2") (pinfunction "2_2") (pintype "passive"))
      (node (ref "R23") (pin "1") (pinfunction "1_1") (pintype "passive"))
    )
    (net (code "33") (name "Net-(Q2-D)") (class "Default")
      (node (ref "Q2") (pin "3") (pinfunction "D_3") (pintype "passive"))
      (node (ref "SP1") (pin "2") (pinfunction "2_2") (pintype "passive"))
    )
    (net (code "34") (name "Net-(Q2-G)") (class "Default")
      (node (ref "Q2") (pin "1") (pinfunction "G_1") (pintype "passive"))
      (node (ref "R24") (pin "2") (pinfunction "2_2") (pintype "passive"))
      (node (ref "R25") (pin "1") (pinfunction "1_1") (pintype "passive"))
    )
    (net (code "35") (name "Net-(Q3-D)") (class "Default")
      (node (ref "Q3") (pin "3") (pinfunction "D_3") (pintype "passive"))
      (node (ref "U1") (pin "2") (pinfunction "2_2") (pintype "bidirectional"))
      (node (ref "U2") (pin "2") (pinfunction "2_2") (pintype "bidirectional"))
      (node (ref "U3") (pin "2") (pinfunction "2_2") (pintype "bidirectional"))
      (node (ref "U4") (pin "2") (pinfunction "2_2") (pintype "bidirectional"))
      (node (ref "U5") (pin "2") (pinfunction "2_2") (pintype "bidirectional"))
    )
    (net (code "36") (name "Net-(Q3-G)") (class "Default")
      (node (ref "Q3") (pin "1") (pinfunction "G_1") (pintype "passive"))
      (node (ref "R30") (pin "2") (pinfunction "2_2") (pintype "passive"))
      (node (ref "R33") (pin "1") (pinfunction "1_1") (pintype "passive"))
    )
    (net (code "37") (name "Net-(Q4-B)") (class "Default")
      (node (ref "Q4") (pin "1") (pinfunction "B_1") (pintype "passive"))
      (node (ref "R34") (pin "2") (pinfunction "2_2") (pintype "passive"))
    )
    (net (code "38") (name "Net-(Q4-E)") (class "Default")
      (node (ref "Q4") (pin "2") (pinfunction "E_2") (pintype "passive"))
      (node (ref "R35") (pin "1") (pinfunction "1_1") (pintype "passive"))
      (node (ref "U$5") (pin "14") (pinfunction "RTS_14") (pintype "bidirectional"))
    )
    (net (code "39") (name "Net-(Q5-B)") (class "Default")
      (node (ref "Q5") (pin "1") (pinfunction "B_1") (pintype "passive"))
      (node (ref "R35") (pin "2") (pinfunction "2_2") (pintype "passive"))
    )
    (net (code "40") (name "Net-(Q5-E)") (class "Default")
      (node (ref "Q5") (pin "2") (pinfunction "E_2") (pintype "passive"))
      (node (ref "R34") (pin "1") (pinfunction "1_1") (pintype "passive"))
      (node (ref "U$5") (pin "13") (pinfunction "DTR_13") (pintype "bidirectional"))
    )
    (net (code "41") (name "Net-(R3-Pad2)") (class "Default")
      (node (ref "R3") (pin "2") (pinfunction "2_2") (pintype "passive"))
      (node (ref "SP1") (pin "1") (pinfunction "1_1") (pintype "passive"))
    )
    (net (code "42") (name "Net-(R6-Pad2)") (class "Default")
      (node (ref "R6") (pin "2") (pinfunction "2_2") (pintype "passive"))
      (node (ref "U3") (pin "1") (pinfunction "1_1") (pintype "bidirectional"))
    )
    (net (code "43") (name "Net-(R7-Pad2)") (class "Default")
      (node (ref "R7") (pin "2") (pinfunction "2_2") (pintype "passive"))
      (node (ref "U$2") (pin "CH_PD") (pinfunction "CH_PD_CH_PD") (pintype "bidirectional"))
    )
    (net (code "44") (name "Net-(R10-Pad2)") (class "Default")
      (node (ref "R10") (pin "2") (pinfunction "2_2") (pintype "passive"))
      (node (ref "U4") (pin "1") (pinfunction "1_1") (pintype "bidirectional"))
    )
    (net (code "45") (name "Net-(R11-Pad2)") (class "Default")
      (node (ref "R11") (pin "2") (pinfunction "2_2") (pintype "passive"))
      (node (ref "U5") (pin "1") (pinfunction "1_1") (pintype "bidirectional"))
    )
    (net (code "46") (name "Net-(R12-Pad2)") (class "Default")
      (node (ref "R12") (pin "2") (pinfunction "2_2") (pintype "passive"))
      (node (ref "U1") (pin "1") (pinfunction "1_1") (pintype "bidirectional"))
    )
    (net (code "47") (name "Net-(R13-Pad2)") (class "Default")
      (node (ref "R13") (pin "2") (pinfunction "2_2") (pintype "passive"))
      (node (ref "U2") (pin "1") (pinfunction "1_1") (pintype "bidirectional"))
    )
    (net (code "48") (name "Net-(RGB1-DO)") (class "Default")
      (node (ref "RGB") (pin "2") (pinfunction "2_2") (pintype "passive"))
      (node (ref "RGB1") (pin "P2") (pinfunction "DO_P2") (pintype "output"))
    )
    (net (code "49") (name "Net-(RGB1-LEDVDD)") (class "Default")
      (node (ref "C13") (pin "1") (pinfunction "1_1") (pintype "passive"))
      (node (ref "D1") (pin "C") (pinfunction "C_C") (pintype "passive"))
      (node (ref "RGB1") (pin "P1") (pinfunction "LEDVDD_P1") (pintype "power_in"))
    )
    (net (code "50") (name "Net-(S1-O)") (class "Default")
      (node (ref "JP3") (pin "2") (pinfunction "2_2") (pintype "passive"))
      (node (ref "S1") (pin "1") (pinfunction "O_1") (pintype "passive"))
    )
    (net (code "51") (name "Net-(U$5-D+)") (class "Default")
      (node (ref "U$5") (pin "5") (pinfunction "D+_5") (pintype "bidirectional"))
      (node (ref "USB1") (pin "D+") (pinfunction "D+_D+") (pintype "bidirectional"))
    )
    (net (code "52") (name "Net-(U$5-D-)") (class "Default")
      (node (ref "U$5") (pin "6") (pinfunction "D-_6") (pintype "bidirectional"))
      (node (ref "USB1") (pin "D-") (pinfunction "D-_D-") (pintype "bidirectional"))
    )
    (net (code "53") (name "Net-(U$5-RX)") (class "Default")
      (node (ref "R32") (pin "1") (pinfunction "1_1") (pintype "passive"))
      (node (ref "U$5") (pin "3") (pinfunction "RX_3") (pintype "bidirectional"))
    )
    (net (code "54") (name "Net-(U$5-TX)") (class "Default")
      (node (ref "R31") (pin "1") (pinfunction "1_1") (pintype "passive"))
      (node (ref "U$5") (pin "2") (pinfunction "TX_2") (pintype "bidirectional"))
    )
    (net (code "55") (name "Net-(U$5-V3)") (class "Default")
      (node (ref "C21") (pin "1") (pinfunction "1_1") (pintype "passive"))
      (node (ref "U$5") (pin "4") (pinfunction "V3_4") (pintype "bidirectional"))
    )
    (net (code "56") (name "Net-(U$5-XI)") (class "Default")
      (node (ref "C26") (pin "1") (pinfunction "1_1") (pintype "passive"))
      (node (ref "U$5") (pin "7") (pinfunction "XI_7") (pintype "bidirectional"))
      (node (ref "X1") (pin "1") (pinfunction "1_1") (pintype "passive"))
    )
    (net (code "57") (name "Net-(U$5-XO)") (class "Default")
      (node (ref "C29") (pin "1") (pinfunction "1_1") (pintype "passive"))
      (node (ref "U$5") (pin "8") (pinfunction "XO_8") (pintype "bidirectional"))
      (node (ref "X1") (pin "2") (pinfunction "2_2") (pintype "passive"))
    )
    (net (code "58") (name "OPTO") (class "Default")
      (node (ref "IRX1") (pin "OUT@1") (pinfunction "OUT_OUT@1") (pintype "bidirectional"))
      (node (ref "IRX2") (pin "OUT@1") (pinfunction "OUT_OUT@1") (pintype "bidirectional"))
      (node (ref "R19") (pin "1") (pinfunction "1_1") (pintype "passive"))
      (node (ref "U$2") (pin "GPIO5") (pinfunction "GPIO5_GPIO5") (pintype "bidirectional"))
    )
    (net (code "59") (name "PROG") (class "Default")
      (node (ref "Q5") (pin "3") (pinfunction "C_3") (pintype "passive"))
      (node (ref "R17") (pin "2") (pinfunction "2_2") (pintype "passive"))
      (node (ref "U$2") (pin "GPIO0") (pinfunction "GPIO0_GPIO0") (pintype "bidirectional"))
    )
    (net (code "60") (name "RESET") (class "Default")
      (node (ref "Q4") (pin "3") (pinfunction "C_3") (pintype "passive"))
      (node (ref "R22") (pin "2") (pinfunction "2_2") (pintype "passive"))
      (node (ref "R8") (pin "1") (pinfunction "1_1") (pintype "passive"))
      (node (ref "U$2") (pin "RESET") (pinfunction "RESET_RESET") (pintype "bidirectional"))
    )
    (net (code "61") (name "RX") (class "Default")
      (node (ref "R31") (pin "2") (pinfunction "2_2") (pintype "passive"))
      (node (ref "U$2") (pin "RX") (pinfunction "RX_RX") (pintype "bidirectional"))
    )
    (net (code "62") (name "SCL") (class "Default")
      (node (ref "R26") (pin "2") (pinfunction "2_2") (pintype "passive"))
      (node (ref "U$2") (pin "GPIO2") (pinfunction "GPIO2_GPIO2") (pintype "bidirectional"))
      (node (ref "U6") (pin "25") (pinfunction "SCL_25") (pintype "bidirectional"))
    )
    (net (code "63") (name "SDA") (class "Default")
      (node (ref "R27") (pin "2") (pinfunction "2_2") (pintype "passive"))
      (node (ref "U$2") (pin "GPIO14") (pinfunction "GPIO14_GPIO14") (pintype "bidirectional"))
      (node (ref "U6") (pin "24") (pinfunction "SDA_24") (pintype "bidirectional"))
    )
    (net (code "64") (name "SENS") (class "Default")
      (node (ref "R30") (pin "1") (pinfunction "1_1") (pintype "passive"))
      (node (ref "U6") (pin "15") (pinfunction "I/O[10]_15") (pintype "bidirectional"))
    )
    (net (code "65") (name "SPKR") (class "Default")
      (node (ref "R24") (pin "1") (pinfunction "1_1") (pintype "passive"))
      (node (ref "U$2") (pin "GPIO13") (pinfunction "GPIO13_GPIO13") (pintype "bidirectional"))
    )
    (net (code "66") (name "TX") (class "Default")
      (node (ref "R32") (pin "2") (pinfunction "2_2") (pintype "passive"))
      (node (ref "U$2") (pin "TX") (pinfunction "TX_TX") (pintype "bidirectional"))
    )
    (net (code "67") (name "VCC") (class "Default")
      (node (ref "C10") (pin "1") (pinfunction "1_1") (pintype "passive"))
      (node (ref "C2") (pin "1") (pinfunction "1_1") (pintype "passive"))
      (node (ref "C20") (pin "1") (pinfunction "1_1") (pintype "passive"))
      (node (ref "C24") (pin "1") (pinfunction "1_1") (pintype "passive"))
      (node (ref "C8") (pin "1") (pinfunction "1_1") (pintype "passive"))
      (node (ref "C9") (pin "1") (pinfunction "1_1") (pintype "passive"))
      (node (ref "IC8") (pin "2") (pinfunction "VOUT_2") (pintype "output"))
      (node (ref "JP11") (pin "4") (pinfunction "4_4") (pintype "passive"))
      (node (ref "JP12") (pin "4") (pinfunction "4_4") (pintype "passive"))
      (node (ref "JP13") (pin "3") (pinfunction "3_3") (pintype "passive"))
      (node (ref "JP13") (pin "4") (pinfunction "4_4") (pintype "passive"))
      (node (ref "JP15") (pin "4") (pinfunction "4_4") (pintype "passive"))
      (node (ref "JP16") (pin "2") (pinfunction "2_2") (pintype "passive"))
      (node (ref "JP16") (pin "3") (pinfunction "3_3") (pintype "passive"))
      (node (ref "JP5") (pin "13") (pinfunction "13_13") (pintype "passive"))
      (node (ref "JP5") (pin "14") (pinfunction "14_14") (pintype "passive"))
      (node (ref "JP5") (pin "21") (pinfunction "21_21") (pintype "passive"))
      (node (ref "JP5") (pin "22") (pinfunction "22_22") (pintype "passive"))
      (node (ref "JP5") (pin "29") (pinfunction "29_29") (pintype "passive"))
      (node (ref "JP5") (pin "30") (pinfunction "30_30") (pintype "passive"))
      (node (ref "JP5") (pin "37") (pinfunction "37_37") (pintype "passive"))
      (node (ref "JP5") (pin "38") (pinfunction "38_38") (pintype "passive"))
      (node (ref "JP5") (pin "45") (pinfunction "45_45") (pintype "passive"))
      (node (ref "JP5") (pin "46") (pinfunction "46_46") (pintype "passive"))
      (node (ref "JP5") (pin "5") (pinfunction "5_5") (pintype "passive"))
      (node (ref "JP5") (pin "53") (pinfunction "53_53") (pintype "passive"))
      (node (ref "JP5") (pin "54") (pinfunction "54_54") (pintype "passive"))
      (node (ref "JP5") (pin "6") (pinfunction "6_6") (pintype "passive"))
      (node (ref "JP6") (pin "13") (pinfunction "13_13") (pintype "passive"))
      (node (ref "JP6") (pin "14") (pinfunction "14_14") (pintype "passive"))
      (node (ref "JP6") (pin "21") (pinfunction "21_21") (pintype "passive"))
      (node (ref "JP6") (pin "22") (pinfunction "22_22") (pintype "passive"))
      (node (ref "JP6") (pin "29") (pinfunction "29_29") (pintype "passive"))
      (node (ref "JP6") (pin "30") (pinfunction "30_30") (pintype "passive"))
      (node (ref "JP6") (pin "37") (pinfunction "37_37") (pintype "passive"))
      (node (ref "JP6") (pin "38") (pinfunction "38_38") (pintype "passive"))
      (node (ref "JP6") (pin "45") (pinfunction "45_45") (pintype "passive"))
      (node (ref "JP6") (pin "46") (pinfunction "46_46") (pintype "passive"))
      (node (ref "JP6") (pin "5") (pinfunction "5_5") (pintype "passive"))
      (node (ref "JP6") (pin "53") (pinfunction "53_53") (pintype "passive"))
      (node (ref "JP6") (pin "54") (pinfunction "54_54") (pintype "passive"))
      (node (ref "JP6") (pin "6") (pinfunction "6_6") (pintype "passive"))
      (node (ref "JP8") (pin "11") (pinfunction "11_11") (pintype "passive"))
      (node (ref "JP8") (pin "6") (pinfunction "6_6") (pintype "passive"))
      (node (ref "LED1") (pin "A") (pinfunction "A_A") (pintype "passive"))
      (node (ref "R1") (pin "1") (pinfunction "1_1") (pintype "passive"))
      (node (ref "R10") (pin "1") (pinfunction "1_1") (pintype "passive"))
      (node (ref "R11") (pin "1") (pinfunction "1_1") (pintype "passive"))
      (node (ref "R12") (pin "1") (pinfunction "1_1") (pintype "passive"))
      (node (ref "R13") (pin "1") (pinfunction "1_1") (pintype "passive"))
      (node (ref "R14") (pin "2") (pinfunction "2_2") (pintype "passive"))
      (node (ref "R15") (pin "2") (pinfunction "2_2") (pintype "passive"))
      (node (ref "R16") (pin "2") (pinfunction "2_2") (pintype "passive"))
      (node (ref "R17") (pin "1") (pinfunction "1_1") (pintype "passive"))
      (node (ref "R18") (pin "2") (pinfunction "2_2") (pintype "passive"))
      (node (ref "R19") (pin "2") (pinfunction "2_2") (pintype "passive"))
      (node (ref "R2") (pin "1") (pinfunction "1_1") (pintype "passive"))
      (node (ref "R22") (pin "1") (pinfunction "1_1") (pintype "passive"))
      (node (ref "R26") (pin "1") (pinfunction "1_1") (pintype "passive"))
      (node (ref "R27") (pin "1") (pinfunction "1_1") (pintype "passive"))
      (node (ref "R3") (pin "1") (pinfunction "1_1") (pintype "passive"))
      (node (ref "R4") (pin "2") (pinfunction "2_2") (pintype "passive"))
      (node (ref "R5") (pin "2") (pinfunction "2_2") (pintype "passive"))
      (node (ref "R6") (pin "1") (pinfunction "1_1") (pintype "passive"))
      (node (ref "R7") (pin "1") (pinfunction "1_1") (pintype "passive"))
      (node (ref "R9") (pin "1") (pinfunction "1_1") (pintype "passive"))
      (node (ref "U$2") (pin "VCC") (pinfunction "VCC_VCC") (pintype "bidirectional"))
      (node (ref "U6") (pin "12") (pinfunction "VDDM_12") (pintype "bidirectional"))
      (node (ref "U6") (pin "18") (pinfunction "VCC2_18") (pintype "bidirectional"))
      (node (ref "U6") (pin "23") (pinfunction "~{RESET}_23") (pintype "bidirectional"))
    )
    (net (code "68") (name "VUSB") (class "Default")
      (node (ref "C22") (pin "1") (pinfunction "1_1") (pintype "passive"))
      (node (ref "C23") (pin "1") (pinfunction "1_1") (pintype "passive"))
      (node (ref "S1") (pin "3") (pinfunction "S_3") (pintype "passive"))
      (node (ref "U$5") (pin "16") (pinfunction "VCC_16") (pintype "bidirectional"))
      (node (ref "USB1") (pin "VBUS") (pinfunction "VBUS_VBUS") (pintype "bidirectional"))
    )
    (net (code "69") (name "unconnected-(JP15-Pad1)") (class "Default")
      (node (ref "JP15") (pin "1") (pinfunction "1_1") (pintype "passive"))
    )
    (net (code "70") (name "unconnected-(U$5-CTS-Pad9)") (class "Default")
      (node (ref "U$5") (pin "9") (pinfunction "CTS_9") (pintype "bidirectional"))
    )
    (net (code "71") (name "unconnected-(U$5-DCD-Pad12)") (class "Default")
      (node (ref "U$5") (pin "12") (pinfunction "DCD_12") (pintype "bidirectional"))
    )
    (net (code "72") (name "unconnected-(U$5-DSR-Pad10)") (class "Default")
      (node (ref "U$5") (pin "10") (pinfunction "DSR_10") (pintype "bidirectional"))
    )
    (net (code "73") (name "unconnected-(U$5-RI-Pad11)") (class "Default")
      (node (ref "U$5") (pin "11") (pinfunction "RI_11") (pintype "bidirectional"))
    )
    (net (code "74") (name "unconnected-(U$5-RS232-Pad15)") (class "Default")
      (node (ref "U$5") (pin "15") (pinfunction "RS232_15") (pintype "bidirectional"))
    )
    (net (code "75") (name "unconnected-(U6-OSCIO-Pad11)") (class "Default")
      (node (ref "U6") (pin "11") (pinfunction "OSCIO_11") (pintype "bidirectional"))
    )
    (net (code "76") (name "unconnected-(USB1-PadID)") (class "Default")
      (node (ref "USB1") (pin "ID") (pinfunction "ID_ID") (pintype "bidirectional"))
    )
  )
)
